# ArduinoProgrammer.net
KiCad netlist of a schematic drawn in EAGLE
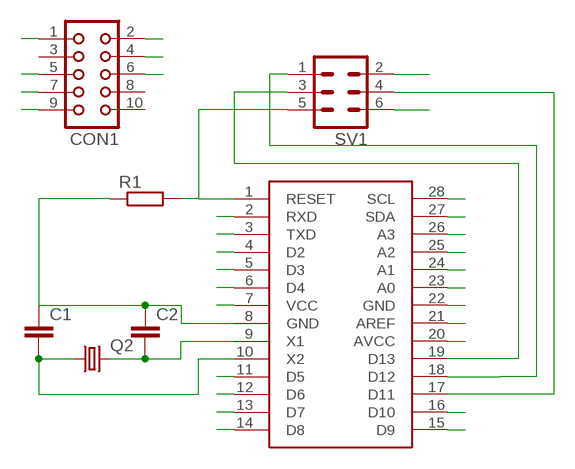
[diagram p0: schematic, sheet 1]

(export (version "E")
  (design (tool "Eeschema 10.0.6"))
  (components
    (comp (ref "C1")
      (value "C-EU025-024X044")
      (footprint "eagle-import:C025-024X044")
      (libsource (lib "eagle-import") (part "C-EU025-024X044"))
    )
    (comp (ref "C2")
      (value "C-EU025-024X044")
      (footprint "eagle-import:C025-024X044")
      (libsource (lib "eagle-import") (part "C-EU025-024X044"))
    )
    (comp (ref "CON1")
      (value "CON10")
      (footprint "eagle-import:CON10")
      (libsource (lib "eagle-import") (part "CON10"))
    )
    (comp (ref "Q2")
      (value "CRYSTALHC49S")
      (footprint "eagle-import:HC49_S")
      (libsource (lib "eagle-import") (part "CRYSTALHC49S"))
    )
    (comp (ref "R1")
      (value "R-EU_0207/10")
      (footprint "eagle-import:0207_10")
      (libsource (lib "eagle-import") (part "R-EU_0207/10"))
    )
    (comp (ref "SV1")
      (value "MA03-2")
      (footprint "eagle-import:MA03-2")
      (libsource (lib "eagle-import") (part "MA03-2"))
    )
    (comp (ref "U$1")
      (value "ATMEGA328P-PU")
      (footprint "eagle-import:DIL28-3")
      (libsource (lib "eagle-import") (part "ATMEGA328P-PU"))
    )
  )
  (nets
    (net (code "1") (name "/DIO11(PWM)MOSI[HR]") (class "Default")
      (node (ref "CON1") (pin "1") (pinfunction "1_1") (pintype "passive"))
      (node (ref "SV1") (pin "4") (pinfunction "4_4") (pintype "passive"))
      (node (ref "U$1") (pin "17") (pinfunction "D11_17") (pintype "bidirectional"))
    )
    (net (code "2") (name "/DIO12{slash}MISO[L4]") (class "Default")
      (node (ref "CON1") (pin "9") (pinfunction "9_9") (pintype "passive"))
      (node (ref "SV1") (pin "1") (pinfunction "1_1") (pintype "passive"))
      (node (ref "U$1") (pin "18") (pinfunction "D12_18") (pintype "bidirectional"))
    )
    (net (code "3") (name "/GND") (class "Default")
      (node (ref "C1") (pin "1") (pinfunction "1_1") (pintype "passive"))
      (node (ref "C2") (pin "1") (pinfunction "1_1") (pintype "passive"))
      (node (ref "CON1") (pin "4") (pinfunction "4_4") (pintype "passive"))
      (node (ref "R1") (pin "1") (pinfunction "1_1") (pintype "passive"))
      (node (ref "SV1") (pin "6") (pinfunction "6_6") (pintype "passive"))
      (node (ref "U$1") (pin "22") (pinfunction "GND_22") (pintype "bidirectional"))
      (node (ref "U$1") (pin "8") (pinfunction "GND_8") (pintype "bidirectional"))
    )
    (net (code "4") (name "/SCK[L5]") (class "Default")
      (node (ref "CON1") (pin "7") (pinfunction "7_7") (pintype "passive"))
      (node (ref "SV1") (pin "3") (pinfunction "3_3") (pintype "passive"))
      (node (ref "U$1") (pin "19") (pinfunction "D13_19") (pintype "bidirectional"))
    )
    (net (code "5") (name "/VCC") (class "Default")
      (node (ref "CON1") (pin "2") (pinfunction "2_2") (pintype "passive"))
      (node (ref "SV1") (pin "2") (pinfunction "2_2") (pintype "passive"))
      (node (ref "U$1") (pin "20") (pinfunction "AVCC_20") (pintype "bidirectional"))
      (node (ref "U$1") (pin "7") (pinfunction "VCC_7") (pintype "bidirectional"))
    )
    (net (code "6") (name "Net-(U$1-RESET)") (class "Default")
      (node (ref "R1") (pin "2") (pinfunction "2_2") (pintype "passive"))
      (node (ref "SV1") (pin "5") (pinfunction "5_5") (pintype "passive"))
      (node (ref "U$1") (pin "1") (pinfunction "RESET_1") (pintype "bidirectional"))
    )
    (net (code "7") (name "Net-(U$1-X1)") (class "Default")
      (node (ref "C2") (pin "2") (pinfunction "2_2") (pintype "passive"))
      (node (ref "Q2") (pin "2") (pinfunction "2_2") (pintype "passive"))
      (node (ref "U$1") (pin "9") (pinfunction "X1_9") (pintype "bidirectional"))
    )
    (net (code "8") (name "Net-(U$1-X2)") (class "Default")
      (node (ref "C1") (pin "2") (pinfunction "2_2") (pintype "passive"))
      (node (ref "Q2") (pin "1") (pinfunction "1_1") (pintype "passive"))
      (node (ref "U$1") (pin "10") (pinfunction "X2_10") (pintype "bidirectional"))
    )
    (net (code "9") (name "unconnected-(CON1-Pad3)") (class "Default")
      (node (ref "CON1") (pin "3") (pinfunction "3_3") (pintype "passive"))
    )
    (net (code "10") (name "unconnected-(CON1-Pad5)") (class "Default")
      (node (ref "CON1") (pin "5") (pinfunction "5_5") (pintype "passive"))
    )
    (net (code "11") (name "unconnected-(CON1-Pad6)") (class "Default")
      (node (ref "CON1") (pin "6") (pinfunction "6_6") (pintype "passive"))
    )
    (net (code "12") (name "unconnected-(CON1-Pad8)") (class "Default")
      (node (ref "CON1") (pin "8") (pinfunction "8_8") (pintype "passive"))
    )
    (net (code "13") (name "unconnected-(CON1-Pad10)") (class "Default")
      (node (ref "CON1") (pin "10") (pinfunction "10_10") (pintype "passive"))
    )
    (net (code "14") (name "unconnected-(U$1-A0-Pad23)") (class "Default")
      (node (ref "U$1") (pin "23") (pinfunction "A0_23") (pintype "bidirectional"))
    )
    (net (code "15") (name "unconnected-(U$1-A1-Pad24)") (class "Default")
      (node (ref "U$1") (pin "24") (pinfunction "A1_24") (pintype "bidirectional"))
    )
    (net (code "16") (name "unconnected-(U$1-A2-Pad25)") (class "Default")
      (node (ref "U$1") (pin "25") (pinfunction "A2_25") (pintype "bidirectional"))
    )
    (net (code "17") (name "unconnected-(U$1-A3-Pad26)") (class "Default")
      (node (ref "U$1") (pin "26") (pinfunction "A3_26") (pintype "bidirectional"))
    )
    (net (code "18") (name "unconnected-(U$1-AREF-Pad21)") (class "Default")
      (node (ref "U$1") (pin "21") (pinfunction "AREF_21") (pintype "bidirectional"))
    )
    (net (code "19") (name "unconnected-(U$1-D2-Pad4)") (class "Default")
      (node (ref "U$1") (pin "4") (pinfunction "D2_4") (pintype "bidirectional"))
    )
    (net (code "20") (name "unconnected-(U$1-D3-Pad5)") (class "Default")
      (node (ref "U$1") (pin "5") (pinfunction "D3_5") (pintype "bidirectional"))
    )
    (net (code "21") (name "unconnected-(U$1-D4-Pad6)") (class "Default")
      (node (ref "U$1") (pin "6") (pinfunction "D4_6") (pintype "bidirectional"))
    )
    (net (code "22") (name "unconnected-(U$1-D5-Pad11)") (class "Default")
      (node (ref "U$1") (pin "11") (pinfunction "D5_11") (pintype "bidirectional"))
    )
    (net (code "23") (name "unconnected-(U$1-D6-Pad12)") (class "Default")
      (node (ref "U$1") (pin "12") (pinfunction "D6_12") (pintype "bidirectional"))
    )
    (net (code "24") (name "unconnected-(U$1-D7-Pad13)") (class "Default")
      (node (ref "U$1") (pin "13") (pinfunction "D7_13") (pintype "bidirectional"))
    )
    (net (code "25") (name "unconnected-(U$1-D8-Pad14)") (class "Default")
      (node (ref "U$1") (pin "14") (pinfunction "D8_14") (pintype "bidirectional"))
    )
    (net (code "26") (name "unconnected-(U$1-D9-Pad15)") (class "Default")
      (node (ref "U$1") (pin "15") (pinfunction "D9_15") (pintype "bidirectional"))
    )
    (net (code "27") (name "unconnected-(U$1-D10-Pad16)") (class "Default")
      (node (ref "U$1") (pin "16") (pinfunction "D10_16") (pintype "bidirectional"))
    )
    (net (code "28") (name "unconnected-(U$1-RXD-Pad2)") (class "Default")
      (node (ref "U$1") (pin "2") (pinfunction "RXD_2") (pintype "bidirectional"))
    )
    (net (code "29") (name "unconnected-(U$1-SCL-Pad28)") (class "Default")
      (node (ref "U$1") (pin "28") (pinfunction "SCL_28") (pintype "bidirectional"))
    )
    (net (code "30") (name "unconnected-(U$1-SDA-Pad27)") (class "Default")
      (node (ref "U$1") (pin "27") (pinfunction "SDA_27") (pintype "bidirectional"))
    )
    (net (code "31") (name "unconnected-(U$1-TXD-Pad3)") (class "Default")
      (node (ref "U$1") (pin "3") (pinfunction "TXD_3") (pintype "bidirectional"))
    )
  )
)
